# Q_Control.net
KiCad netlist of a schematic drawn in EAGLE
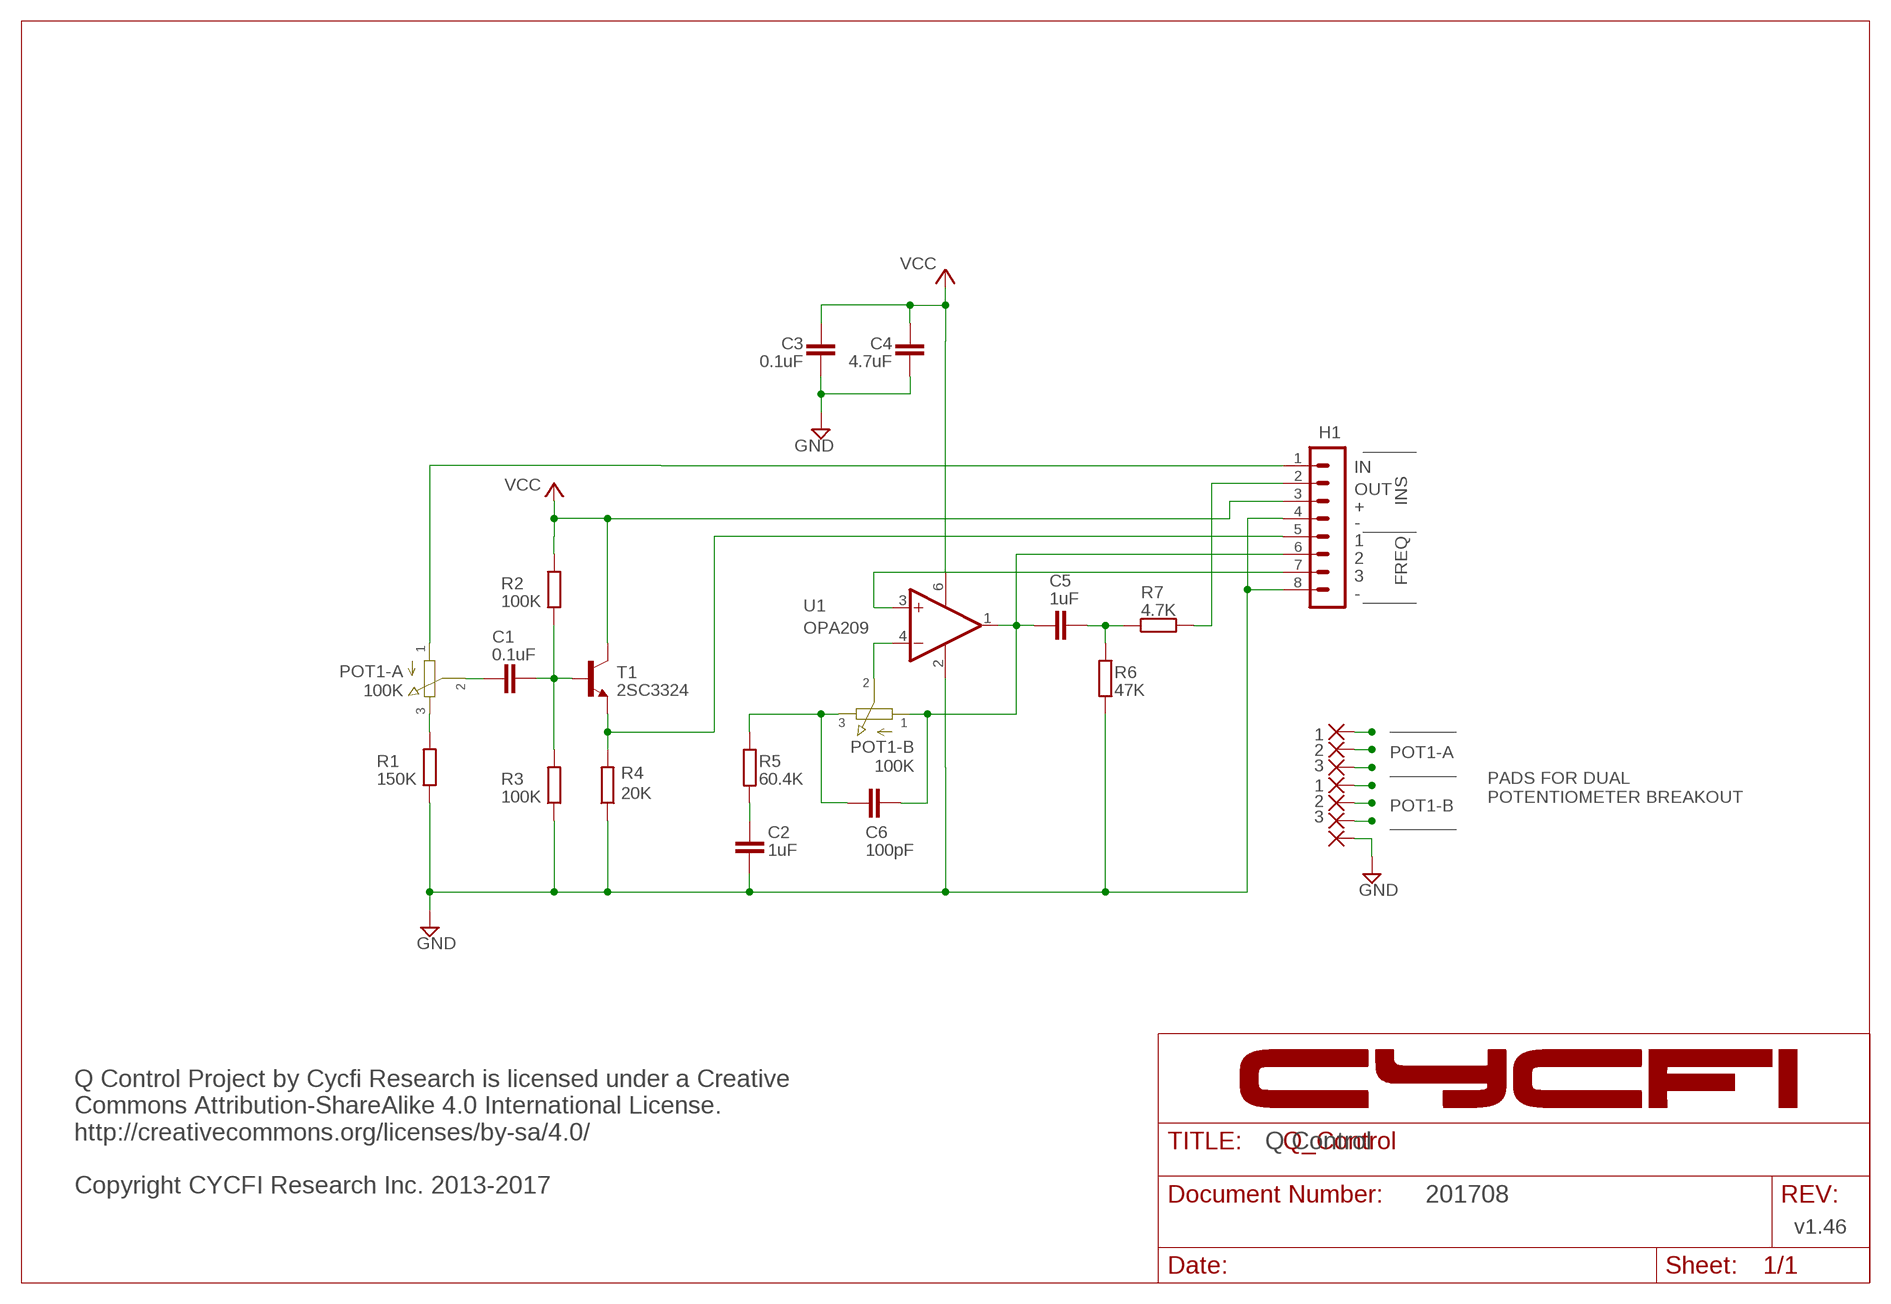
[diagram p0: schematic, sheet 1]

(export (version "E")
  (design (tool "Eeschema 10.0.6"))
  (components
    (comp (ref "C1")
      (value "0.1uF")
      (footprint "eagle-import:C0603")
      (libsource (lib "eagle-import") (part "C-EUC0603"))
    )
    (comp (ref "C2")
      (value "1uF")
      (footprint "eagle-import:C0805")
      (libsource (lib "eagle-import") (part "C-EUC0805"))
    )
    (comp (ref "C3")
      (value "0.1uF")
      (footprint "eagle-import:C0603")
      (libsource (lib "eagle-import") (part "C-EUC0603"))
    )
    (comp (ref "C4")
      (value "4.7uF")
      (footprint "eagle-import:C0603")
      (libsource (lib "eagle-import") (part "C-EUC0603"))
    )
    (comp (ref "C5")
      (value "1uF")
      (footprint "eagle-import:C0805")
      (libsource (lib "eagle-import") (part "C-EUC0805"))
    )
    (comp (ref "C6")
      (value "100pF")
      (footprint "eagle-import:C0805")
      (libsource (lib "eagle-import") (part "C-EUC0805"))
    )
    (comp (ref "H1")
      (value "MA08-1")
      (footprint "eagle-import:MA08-1")
      (libsource (lib "eagle-import") (part "MA08-1"))
    )
    (comp (ref "PAD1")
      (value "SMD2")
      (footprint "eagle-import:SMD1,27-2,54")
      (libsource (lib "eagle-import") (part "SMD2"))
    )
    (comp (ref "PAD2")
      (value "SMD2")
      (footprint "eagle-import:SMD1,27-2,54")
      (libsource (lib "eagle-import") (part "SMD2"))
    )
    (comp (ref "PAD3")
      (value "SMD2")
      (footprint "eagle-import:SMD1,27-2,54")
      (libsource (lib "eagle-import") (part "SMD2"))
    )
    (comp (ref "PAD4")
      (value "SMD2")
      (footprint "eagle-import:SMD1,27-2,54")
      (libsource (lib "eagle-import") (part "SMD2"))
    )
    (comp (ref "PAD5")
      (value "SMD2")
      (footprint "eagle-import:SMD1,27-2,54")
      (libsource (lib "eagle-import") (part "SMD2"))
    )
    (comp (ref "PAD6")
      (value "SMD2")
      (footprint "eagle-import:SMD1,27-2,54")
      (libsource (lib "eagle-import") (part "SMD2"))
    )
    (comp (ref "PAD7")
      (value "SMD2")
      (footprint "eagle-import:SMD1,27-2,54")
      (libsource (lib "eagle-import") (part "SMD2"))
    )
    (comp (ref "R1")
      (value "150K")
      (footprint "eagle-import:R0402")
      (libsource (lib "eagle-import") (part "R-EU_R0402"))
    )
    (comp (ref "R2")
      (value "100K")
      (footprint "eagle-import:R0402")
      (libsource (lib "eagle-import") (part "R-EU_R0402"))
    )
    (comp (ref "R3")
      (value "100K")
      (footprint "eagle-import:R0402")
      (libsource (lib "eagle-import") (part "R-EU_R0402"))
    )
    (comp (ref "R4")
      (value "20K")
      (footprint "eagle-import:R0402")
      (libsource (lib "eagle-import") (part "R-EU_R0402"))
    )
    (comp (ref "R5")
      (value "60.4K")
      (footprint "eagle-import:R0402")
      (libsource (lib "eagle-import") (part "R-EU_R0402"))
    )
    (comp (ref "R6")
      (value "47K")
      (footprint "eagle-import:R0402")
      (libsource (lib "eagle-import") (part "R-EU_R0402"))
    )
    (comp (ref "R7")
      (value "4.7K")
      (footprint "eagle-import:R0402")
      (libsource (lib "eagle-import") (part "R-EU_R0402"))
    )
    (comp (ref "T1")
      (value "2SC3324")
      (footprint "eagle-import:SOT23")
      (libsource (lib "eagle-import") (part "BC846"))
    )
    (comp (ref "U1")
      (value "OPA209")
      (footprint "eagle-import:SOT23-6")
      (libsource (lib "eagle-import") (part "OPA836"))
    )
  )
  (nets
    (net (code "1") (name "/BYP") (class "Default")
      (node (ref "H1") (pin "1") (pinfunction "1_1") (pintype "passive"))
      (node (ref "PAD1") (pin "1") (pinfunction "P_1") (pintype "passive"))
    )
    (net (code "2") (name "/INPUT") (class "Default")
      (node (ref "C1") (pin "1") (pinfunction "1_1") (pintype "passive"))
      (node (ref "PAD2") (pin "1") (pinfunction "P_1") (pintype "passive"))
    )
    (net (code "3") (name "/PA-3") (class "Default")
      (node (ref "PAD3") (pin "1") (pinfunction "P_1") (pintype "passive"))
      (node (ref "R1") (pin "2") (pinfunction "2_2") (pintype "passive"))
    )
    (net (code "4") (name "/PTB-1") (class "Default")
      (node (ref "C5") (pin "2") (pinfunction "2_2") (pintype "passive"))
      (node (ref "C6") (pin "2") (pinfunction "2_2") (pintype "passive"))
      (node (ref "H1") (pin "6") (pinfunction "6_6") (pintype "passive"))
      (node (ref "PAD5") (pin "1") (pinfunction "P_1") (pintype "passive"))
      (node (ref "U1") (pin "1") (pinfunction "OUT_1") (pintype "output"))
    )
    (net (code "5") (name "/PTB-2") (class "Default")
      (node (ref "PAD6") (pin "1") (pinfunction "P_1") (pintype "passive"))
      (node (ref "U1") (pin "4") (pinfunction "-IN_4") (pintype "input"))
    )
    (net (code "6") (name "/PTB-3") (class "Default")
      (node (ref "C6") (pin "1") (pinfunction "1_1") (pintype "passive"))
      (node (ref "PAD4") (pin "1") (pinfunction "P_1") (pintype "passive"))
      (node (ref "R5") (pin "1") (pinfunction "1_1") (pintype "passive"))
    )
    (net (code "7") (name "GND") (class "Default")
      (node (ref "C2") (pin "1") (pinfunction "1_1") (pintype "passive"))
      (node (ref "C3") (pin "1") (pinfunction "1_1") (pintype "passive"))
      (node (ref "C4") (pin "1") (pinfunction "1_1") (pintype "passive"))
      (node (ref "H1") (pin "4") (pinfunction "4_4") (pintype "passive"))
      (node (ref "H1") (pin "8") (pinfunction "8_8") (pintype "passive"))
      (node (ref "PAD7") (pin "1") (pinfunction "P_1") (pintype "passive"))
      (node (ref "R1") (pin "1") (pinfunction "1_1") (pintype "passive"))
      (node (ref "R3") (pin "1") (pinfunction "1_1") (pintype "passive"))
      (node (ref "R4") (pin "1") (pinfunction "1_1") (pintype "passive"))
      (node (ref "R6") (pin "1") (pinfunction "1_1") (pintype "passive"))
      (node (ref "U1") (pin "2") (pinfunction "V-_2") (pintype "power_in"))
    )
    (net (code "8") (name "Net-(C2-Pad2)") (class "Default")
      (node (ref "C2") (pin "2") (pinfunction "2_2") (pintype "passive"))
      (node (ref "R5") (pin "2") (pinfunction "2_2") (pintype "passive"))
    )
    (net (code "9") (name "Net-(C5-Pad1)") (class "Default")
      (node (ref "C5") (pin "1") (pinfunction "1_1") (pintype "passive"))
      (node (ref "R6") (pin "2") (pinfunction "2_2") (pintype "passive"))
      (node (ref "R7") (pin "1") (pinfunction "1_1") (pintype "passive"))
    )
    (net (code "10") (name "Net-(H1-Pad2)") (class "Default")
      (node (ref "H1") (pin "2") (pinfunction "2_2") (pintype "passive"))
      (node (ref "R7") (pin "2") (pinfunction "2_2") (pintype "passive"))
    )
    (net (code "11") (name "Net-(T1-B)") (class "Default")
      (node (ref "C1") (pin "2") (pinfunction "2_2") (pintype "passive"))
      (node (ref "R2") (pin "1") (pinfunction "1_1") (pintype "passive"))
      (node (ref "R3") (pin "2") (pinfunction "2_2") (pintype "passive"))
      (node (ref "T1") (pin "1") (pinfunction "B_1") (pintype "passive"))
    )
    (net (code "12") (name "Net-(T1-E)") (class "Default")
      (node (ref "H1") (pin "5") (pinfunction "5_5") (pintype "passive"))
      (node (ref "R4") (pin "2") (pinfunction "2_2") (pintype "passive"))
      (node (ref "T1") (pin "2") (pinfunction "E_2") (pintype "passive"))
    )
    (net (code "13") (name "Net-(U1-+IN)") (class "Default")
      (node (ref "H1") (pin "7") (pinfunction "7_7") (pintype "passive"))
      (node (ref "U1") (pin "3") (pinfunction "+IN_3") (pintype "input"))
    )
    (net (code "14") (name "VCC") (class "Default")
      (node (ref "C3") (pin "2") (pinfunction "2_2") (pintype "passive"))
      (node (ref "C4") (pin "2") (pinfunction "2_2") (pintype "passive"))
      (node (ref "H1") (pin "3") (pinfunction "3_3") (pintype "passive"))
      (node (ref "R2") (pin "2") (pinfunction "2_2") (pintype "passive"))
      (node (ref "T1") (pin "3") (pinfunction "C_3") (pintype "passive"))
      (node (ref "U1") (pin "6") (pinfunction "V+_6") (pintype "power_in"))
    )
  )
)
